# POWER_STAGE.net
KiCad netlist of a schematic drawn in Altium Designer
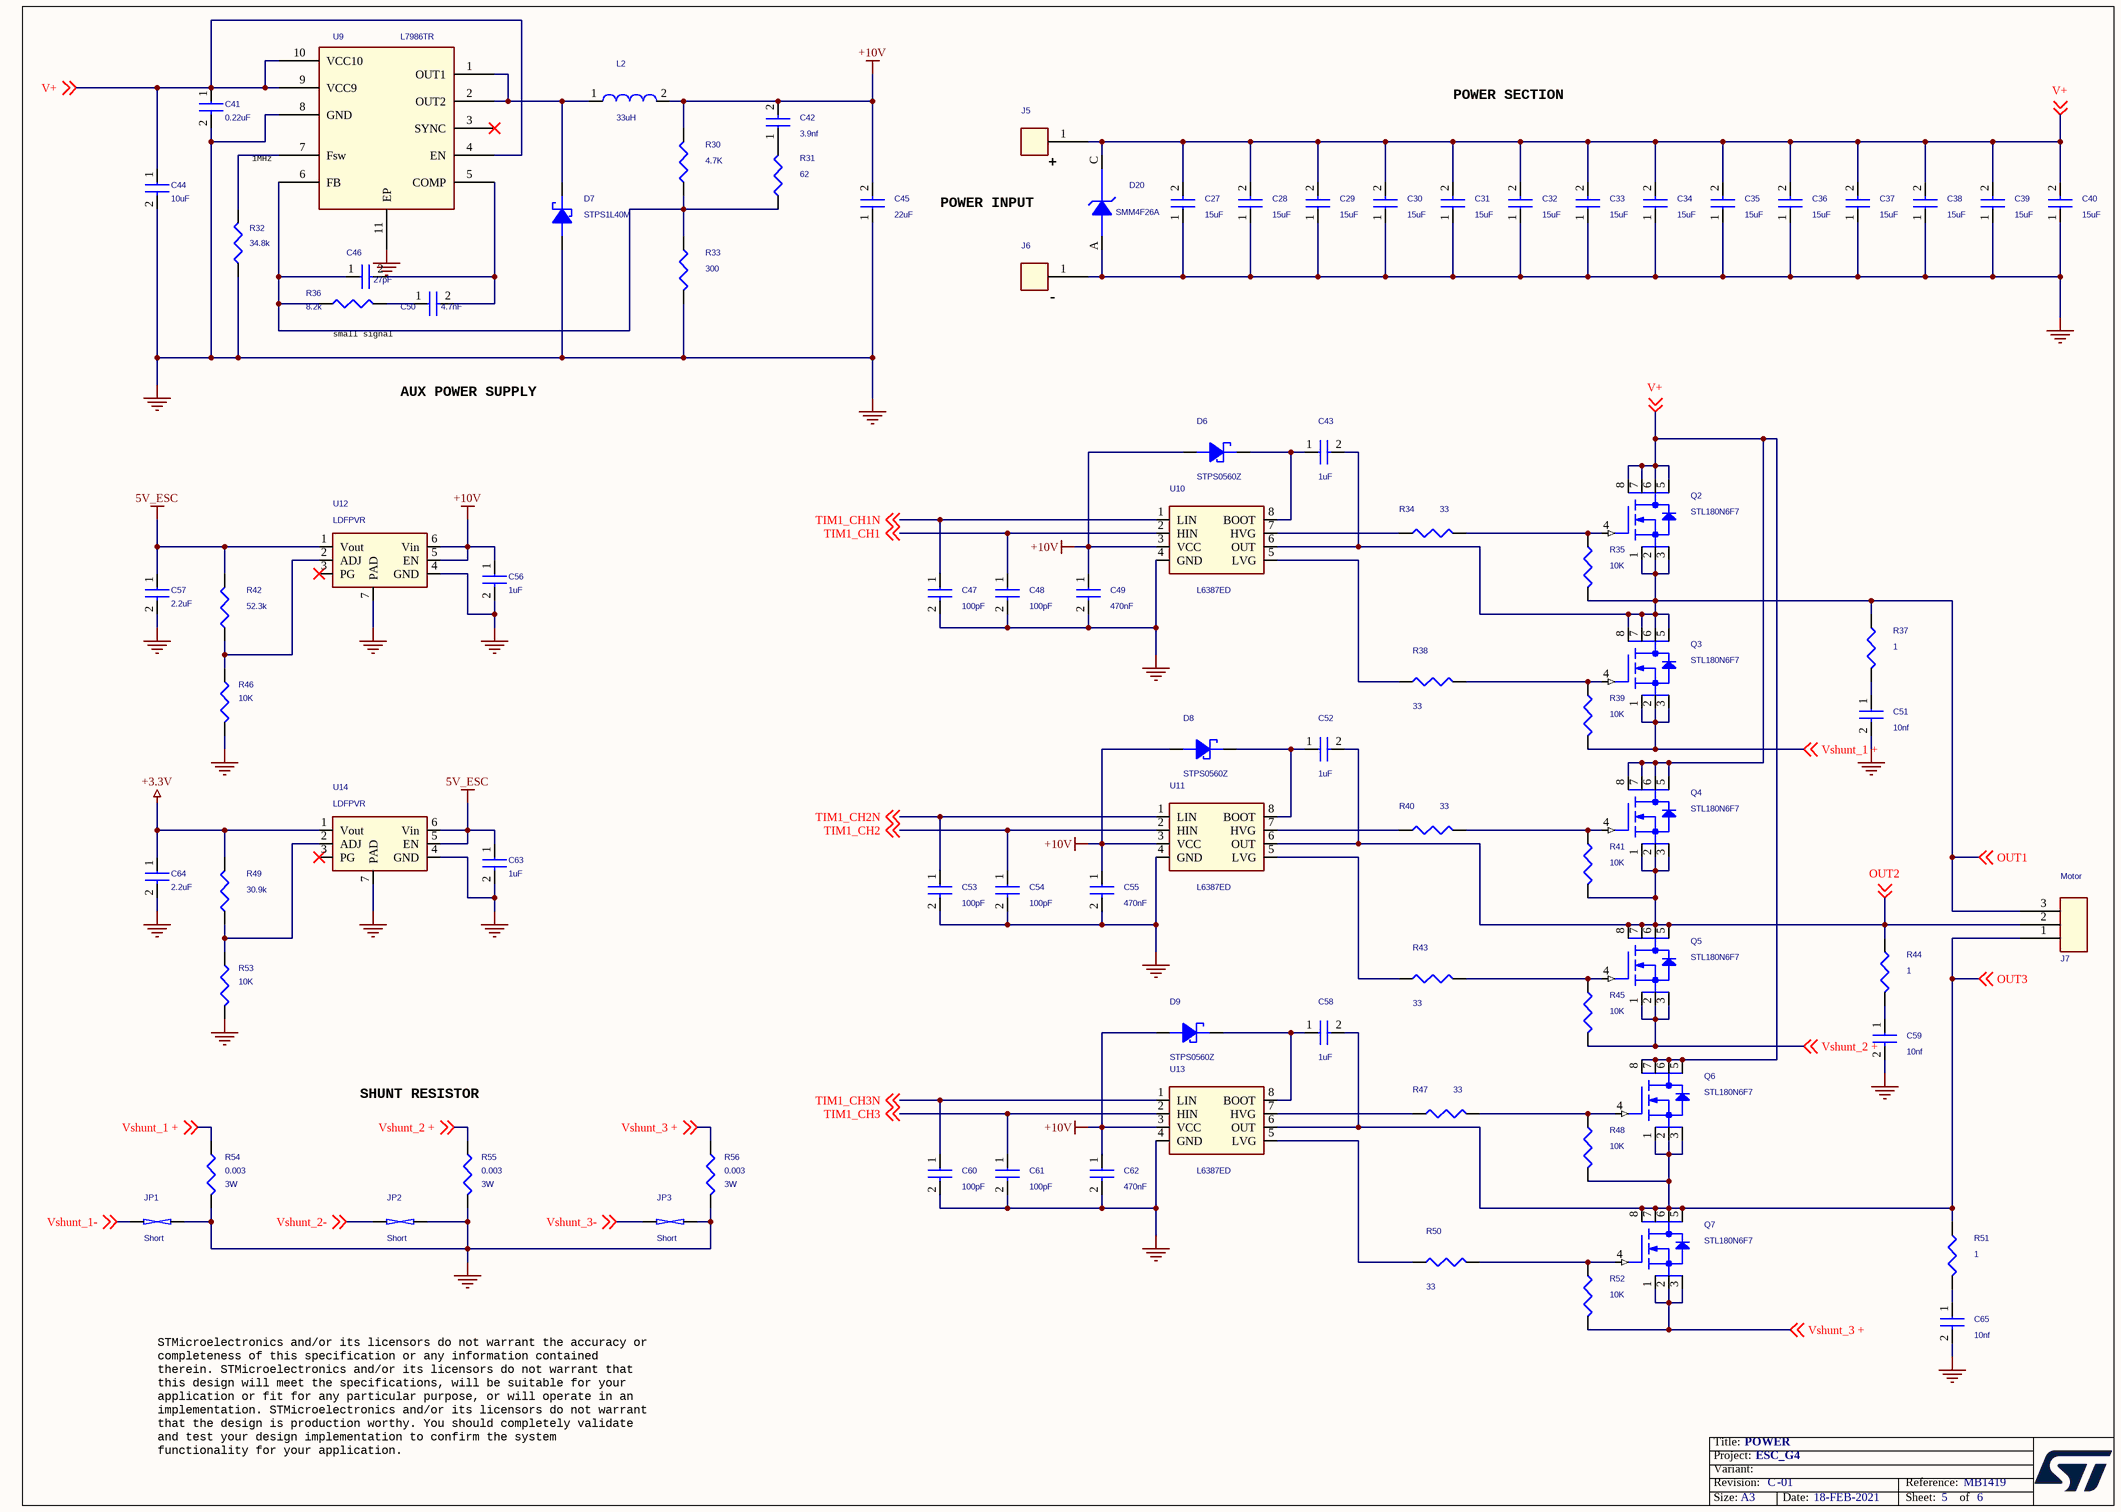
[diagram p0: POWER STAGE.SchDoc]

(export (version "E")
  (design (tool "Eeschema 10.0.6"))
  (components
    (comp (ref "C27")
      (value "15uF")
      (footprint "C_0805_HD")
      (description "CAP CER 15UF 35V X5R 0805")
      (fields (field (name "PART_NUMBER") "TMP-773") (field (name "TOLERANCE") "20%"))
      (libsource (lib "*") (part "CAP_Dup1"))
    )
    (comp (ref "C28")
      (value "15uF")
      (footprint "C_0805_HD")
      (description "CAP CER 15UF 35V X5R 0805")
      (fields (field (name "PART_NUMBER") "TMP-773") (field (name "TOLERANCE") "20%"))
      (libsource (lib "*") (part "CAP_Dup1"))
    )
    (comp (ref "C29")
      (value "15uF")
      (footprint "C_0805_HD")
      (description "CAP CER 15UF 35V X5R 0805")
      (fields (field (name "PART_NUMBER") "TMP-773") (field (name "TOLERANCE") "20%"))
      (libsource (lib "*") (part "CAP_Dup1"))
    )
    (comp (ref "C30")
      (value "15uF")
      (footprint "C_0805_HD")
      (description "CAP CER 15UF 35V X5R 0805")
      (fields (field (name "PART_NUMBER") "TMP-773") (field (name "TOLERANCE") "20%"))
      (libsource (lib "*") (part "CAP_Dup1"))
    )
    (comp (ref "C31")
      (value "15uF")
      (footprint "C_0805_HD")
      (description "CAP CER 15UF 35V X5R 0805")
      (fields (field (name "PART_NUMBER") "TMP-773") (field (name "TOLERANCE") "20%"))
      (libsource (lib "*") (part "CAP_Dup1"))
    )
    (comp (ref "C32")
      (value "15uF")
      (footprint "C_0805_HD")
      (description "CAP CER 15UF 35V X5R 0805")
      (fields (field (name "PART_NUMBER") "TMP-773") (field (name "TOLERANCE") "20%"))
      (libsource (lib "*") (part "CAP_Dup1"))
    )
    (comp (ref "C33")
      (value "15uF")
      (footprint "C_0805_HD")
      (description "CAP CER 15UF 35V X5R 0805")
      (fields (field (name "PART_NUMBER") "TMP-773") (field (name "TOLERANCE") "20%"))
      (libsource (lib "*") (part "CAP_Dup1"))
    )
    (comp (ref "C34")
      (value "15uF")
      (footprint "C_0805_HD")
      (description "CAP CER 15UF 35V X5R 0805")
      (fields (field (name "PART_NUMBER") "TMP-773") (field (name "TOLERANCE") "20%"))
      (libsource (lib "*") (part "CAP_Dup1"))
    )
    (comp (ref "C35")
      (value "15uF")
      (footprint "C_0805_HD")
      (description "CAP CER 15UF 35V X5R 0805")
      (fields (field (name "PART_NUMBER") "TMP-773") (field (name "TOLERANCE") "20%"))
      (libsource (lib "*") (part "CAP_Dup1"))
    )
    (comp (ref "C36")
      (value "15uF")
      (footprint "C_0805_HD")
      (description "CAP CER 15UF 35V X5R 0805")
      (fields (field (name "PART_NUMBER") "TMP-773") (field (name "TOLERANCE") "20%"))
      (libsource (lib "*") (part "CAP_Dup1"))
    )
    (comp (ref "C37")
      (value "15uF")
      (footprint "C_0805_HD")
      (description "CAP CER 15UF 35V X5R 0805")
      (fields (field (name "PART_NUMBER") "TMP-773") (field (name "TOLERANCE") "20%"))
      (libsource (lib "*") (part "CAP_Dup1"))
    )
    (comp (ref "C38")
      (value "15uF")
      (footprint "C_0805_HD")
      (description "CAP CER 15UF 35V X5R 0805")
      (fields (field (name "PART_NUMBER") "TMP-773") (field (name "TOLERANCE") "20%"))
      (libsource (lib "*") (part "CAP_Dup1"))
    )
    (comp (ref "C39")
      (value "15uF")
      (footprint "C_0805_HD")
      (description "CAP CER 15UF 35V X5R 0805")
      (fields (field (name "PART_NUMBER") "TMP-773") (field (name "TOLERANCE") "20%"))
      (libsource (lib "*") (part "CAP_Dup1"))
    )
    (comp (ref "C40")
      (value "15uF")
      (footprint "C_0805_HD")
      (description "CAP CER 15UF 35V X5R 0805")
      (fields (field (name "PART_NUMBER") "TMP-773") (field (name "TOLERANCE") "20%"))
      (libsource (lib "*") (part "CAP_Dup1"))
    )
    (comp (ref "C41")
      (value "0.22uF")
      (footprint "C_0603_HD")
      (description "CAP CER 0.22UF 50V X7R 0603")
      (fields (field (name "MANUFACTURER") "TDK Corporation") (field (name "TOLERANCE") "10%"))
      (libsource (lib "*") (part "CAP_Dup1"))
    )
    (comp (ref "C42")
      (value "3.9nf")
      (footprint "C_0402")
      (description "CAP CER 3900PF 16V X7R 0402")
      (fields (field (name "MANUFACTURER") "KEMET") (field (name "TOLERANCE") "10%"))
      (libsource (lib "*") (part "CAP_Dup1"))
    )
    (comp (ref "C43")
      (value "1uF")
      (footprint "C_0603_HD")
      (description "CAP CER 1UF 25V X7R 0603")
      (fields (field (name "PART_NUMBER") "TMP-446") (field (name "TOLERANCE") "10%"))
      (libsource (lib "*") (part "CAP_Dup1"))
    )
    (comp (ref "C44")
      (value "10uF")
      (footprint "C_1206")
      (description "CAP CER 10UF 50V X7R 1206")
      (fields
        (field (name "MANUFACTURER") "Samsung Electro-Mechanics America, Inc.")
        (field (name "TOLERANCE") "10%")
      )
      (libsource (lib "*") (part "CAP_Dup1"))
    )
    (comp (ref "C45")
      (value "22uF")
      (footprint "C_1206")
      (description "CAP CER 22UF 25V X5R 1206")
      (fields (field (name "MANUFACTURER") "Samsung Electro-Mechanics") (field (name "TOLERANCE") "20%"))
      (libsource (lib "*") (part "CAP_Dup1"))
    )
    (comp (ref "C46")
      (value "27pF")
      (footprint "C_0402")
      (description "CAP CER 27PF 25V C0G/NP0 0402")
      (fields (field (name "MANUFACTURER") "YAGEO") (field (name "TOLERANCE") "5%"))
      (libsource (lib "*") (part "CAP_Dup1"))
    )
    (comp (ref "C47")
      (value "100pF")
      (footprint "C_0402")
      (description "CAP CER 100PF 25V X7R 0402")
      (fields (field (name "PART_NUMBER") "TMP-426") (field (name "TOLERANCE") "10%"))
      (libsource (lib "*") (part "CAP_Dup1"))
    )
    (comp (ref "C48")
      (value "100pF")
      (footprint "C_0402")
      (description "CAP CER 100PF 25V X7R 0402")
      (fields (field (name "PART_NUMBER") "TMP-426") (field (name "TOLERANCE") "10%"))
      (libsource (lib "*") (part "CAP_Dup1"))
    )
    (comp (ref "C49")
      (value "470nF")
      (footprint "C_0603_HD")
      (description "CAP CER 0.47UF 25V X7R 0603")
      (fields (field (name "PART_NUMBER") "TMP-428") (field (name "TOLERANCE") "10%"))
      (libsource (lib "*") (part "CAP_Dup1"))
    )
    (comp (ref "C50")
      (value "4.7nF")
      (footprint "C_0402")
      (description "CAP CER 4700PF 16V X7R 0402")
      (fields (field (name "MANUFACTURER") "Wurth Electronics Inc.") (field (name "TOLERANCE") "10%"))
      (libsource (lib "*") (part "CAP_Dup1"))
    )
    (comp (ref "C51")
      (value "10nf")
      (footprint "C_0603")
      (description "CAP CER 10000PF 100V X7R 0603")
      (fields (field (name "PART_NUMBER") "CAP-00000040") (field (name "TOLERANCE") "20%"))
      (libsource (lib "*") (part "CAP_Dup1"))
    )
    (comp (ref "C52")
      (value "1uF")
      (footprint "C_0603_HD")
      (description "CAP CER 1UF 25V X7R 0603")
      (fields (field (name "PART_NUMBER") "TMP-446") (field (name "TOLERANCE") "10%"))
      (libsource (lib "*") (part "CAP_Dup1"))
    )
    (comp (ref "C53")
      (value "100pF")
      (footprint "C_0402")
      (description "CAP CER 100PF 25V X7R 0402")
      (fields (field (name "PART_NUMBER") "TMP-426") (field (name "TOLERANCE") "10%"))
      (libsource (lib "*") (part "CAP_Dup1"))
    )
    (comp (ref "C54")
      (value "100pF")
      (footprint "C_0402")
      (description "CAP CER 100PF 25V X7R 0402")
      (fields (field (name "PART_NUMBER") "TMP-426") (field (name "TOLERANCE") "10%"))
      (libsource (lib "*") (part "CAP_Dup1"))
    )
    (comp (ref "C55")
      (value "470nF")
      (footprint "C_0603_HD")
      (description "CAP CER 0.47UF 25V X7R 0603")
      (fields (field (name "PART_NUMBER") "TMP-428") (field (name "TOLERANCE") "10%"))
      (libsource (lib "*") (part "CAP_Dup1"))
    )
    (comp (ref "C56")
      (value "1uF")
      (footprint "C_0402")
      (description "CAP CER 1UF 25V X5R 0402")
      (fields
        (field (name "MANUFACTURER") "Murata Electronics North America")
        (field (name "TOLERANCE") "10%")
      )
      (libsource (lib "*") (part "CAP_Dup1"))
    )
    (comp (ref "C57")
      (value "2.2uF")
      (footprint "C_0402")
      (description "CAP CER 2.2UF 10V X5R 0402")
      (fields (field (name "PART_NUMBER") "TMP-449") (field (name "TOLERANCE") "20%"))
      (libsource (lib "*") (part "CAP_Dup1"))
    )
    (comp (ref "C58")
      (value "1uF")
      (footprint "C_0603_HD")
      (description "CAP CER 1UF 25V X7R 0603")
      (fields (field (name "PART_NUMBER") "TMP-446") (field (name "TOLERANCE") "10%"))
      (libsource (lib "*") (part "CAP_Dup1"))
    )
    (comp (ref "C59")
      (value "10nf")
      (footprint "C_0603")
      (description "CAP CER 10000PF 100V X7R 0603")
      (fields (field (name "PART_NUMBER") "CAP-00000040") (field (name "TOLERANCE") "20%"))
      (libsource (lib "*") (part "CAP_Dup1"))
    )
    (comp (ref "C60")
      (value "100pF")
      (footprint "C_0402")
      (description "CAP CER 100PF 25V X7R 0402")
      (fields (field (name "PART_NUMBER") "TMP-426") (field (name "TOLERANCE") "10%"))
      (libsource (lib "*") (part "CAP_Dup1"))
    )
    (comp (ref "C61")
      (value "100pF")
      (footprint "C_0402")
      (description "CAP CER 100PF 25V X7R 0402")
      (fields (field (name "PART_NUMBER") "TMP-426") (field (name "TOLERANCE") "10%"))
      (libsource (lib "*") (part "CAP_Dup1"))
    )
    (comp (ref "C62")
      (value "470nF")
      (footprint "C_0603_HD")
      (description "CAP CER 0.47UF 25V X7R 0603")
      (fields (field (name "PART_NUMBER") "TMP-428") (field (name "TOLERANCE") "10%"))
      (libsource (lib "*") (part "CAP_Dup1"))
    )
    (comp (ref "C63")
      (value "1uF")
      (footprint "C_0402")
      (description "CAP CER 1UF 25V X5R 0402")
      (fields
        (field (name "MANUFACTURER") "Murata Electronics North America")
        (field (name "TOLERANCE") "10%")
      )
      (libsource (lib "*") (part "CAP_Dup1"))
    )
    (comp (ref "C64")
      (value "2.2uF")
      (footprint "C_0402")
      (description "CAP CER 2.2UF 10V X5R 0402")
      (fields (field (name "PART_NUMBER") "TMP-449") (field (name "TOLERANCE") "20%"))
      (libsource (lib "*") (part "CAP_Dup1"))
    )
    (comp (ref "C65")
      (value "10nf")
      (footprint "C_0603")
      (description "CAP CER 10000PF 100V X7R 0603")
      (fields (field (name "PART_NUMBER") "CAP-00000040") (field (name "TOLERANCE") "20%"))
      (libsource (lib "*") (part "CAP_Dup1"))
    )
    (comp (ref "D6")
      (value "STPS0560Z")
      (footprint "SOD_123")
      (description "DIODE SCHOTTKY 60V 500MA SOD123")
      (fields (field (name "MANUFACTURER") "STMicroelectronics") (field (name "PART_NUMBER") "TMP-373"))
      (libsource (lib "*") (part "DIODE_SCHOTTKY_0"))
    )
    (comp (ref "D7")
      (value "STPS1L40M")
      (footprint "do216-aa_stmite")
      (description "DIODE SCHOTTKY 40V 1A STMITE")
      (fields (field (name "PART_NUMBER") "TMP-372") (field (name "MANUFACTURER") "STMicroelectronics"))
      (libsource (lib "*") (part "DIODE_SCHOTTKY_0"))
    )
    (comp (ref "D8")
      (value "STPS0560Z")
      (footprint "SOD_123")
      (description "DIODE SCHOTTKY 60V 500MA SOD123")
      (fields (field (name "MANUFACTURER") "STMicroelectronics") (field (name "PART_NUMBER") "TMP-373"))
      (libsource (lib "*") (part "DIODE_SCHOTTKY_0"))
    )
    (comp (ref "D9")
      (value "STPS0560Z")
      (footprint "SOD_123")
      (description "DIODE SCHOTTKY 60V 500MA SOD123")
      (fields (field (name "MANUFACTURER") "STMicroelectronics") (field (name "PART_NUMBER") "TMP-373"))
      (libsource (lib "*") (part "DIODE_SCHOTTKY_0"))
    )
    (comp (ref "D20")
      (value "SMM4F26A")
      (footprint "do216-aa-flat")
      (description "TVS DIODE 26VWM 53.5VC DO222AA")
      (fields (field (name "MANUFACTURER") "STMicroelectronics") (field (name "PART_NUMBER") "TMP-376"))
      (libsource (lib "*") (part "DIODE_TRANSIL_UNI_0"))
    )
    (comp (ref "J5")
      (value "CON1")
      (footprint "wire1_220s")
      (description "SOLDER PADS")
      (libsource (lib "*") (part "CON1"))
    )
    (comp (ref "J6")
      (value "CON1")
      (footprint "wire1_220s")
      (description "SOLDER PADS")
      (libsource (lib "*") (part "CON1"))
    )
    (comp (ref "J7")
      (value "Motor")
      (footprint "conn_motor_out")
      (description "SOLDER PADS")
      (libsource (lib "*") (part "CON3"))
    )
    (comp (ref "JP1")
      (value "Short")
      (footprint "SHORT")
      (description "2 PIN SHORTED TO CONNECT DIFFERENT NETS")
      (fields (field (name "PART_NUMBER") "TMP-442"))
      (libsource (lib "*") (part "SHORT"))
    )
    (comp (ref "JP2")
      (value "Short")
      (footprint "SHORT")
      (description "2 PIN SHORTED TO CONNECT DIFFERENT NETS")
      (fields (field (name "PART_NUMBER") "TMP-442"))
      (libsource (lib "*") (part "SHORT"))
    )
    (comp (ref "JP3")
      (value "Short")
      (footprint "SHORT")
      (description "2 PIN SHORTED TO CONNECT DIFFERENT NETS")
      (fields (field (name "PART_NUMBER") "TMP-442"))
      (libsource (lib "*") (part "SHORT"))
    )
    (comp (ref "L2")
      (value "33uH")
      (footprint "ind_Coilcraft-LPS4018")
      (description "Fixed Inductors LPS4018 Low Profile 33uH 0.8A 20% SMD")
      (fields (field (name "MANUFACTURER") "Coilcraft") (field (name "TOLERANCE") "20%"))
      (libsource (lib "*") (part "IND"))
    )
    (comp (ref "Q2")
      (value "STL180N6F7")
      (footprint "power_flat_5x6")
      (description "N-channel 60 V, 1.9 mO typ., 120 A STripFET™ F7")
      (fields (field (name "PART_NUMBER") "TMP-772") (field (name "MANUFACTURER") "STMicroelectronics"))
      (libsource (lib "*") (part "MOSFET_N_DIODE_SSSGDDDD"))
    )
    (comp (ref "Q3")
      (value "STL180N6F7")
      (footprint "power_flat_5x6")
      (description "N-channel 60 V, 1.9 mO typ., 120 A STripFET™ F7")
      (fields (field (name "PART_NUMBER") "TMP-772") (field (name "MANUFACTURER") "STMicroelectronics"))
      (libsource (lib "*") (part "MOSFET_N_DIODE_SSSGDDDD"))
    )
    (comp (ref "Q4")
      (value "STL180N6F7")
      (footprint "power_flat_5x6")
      (description "N-channel 60 V, 1.9 mO typ., 120 A STripFET™ F7")
      (fields (field (name "PART_NUMBER") "TMP-772") (field (name "MANUFACTURER") "STMicroelectronics"))
      (libsource (lib "*") (part "MOSFET_N_DIODE_SSSGDDDD"))
    )
    (comp (ref "Q5")
      (value "STL180N6F7")
      (footprint "power_flat_5x6")
      (description "N-channel 60 V, 1.9 mO typ., 120 A STripFET™ F7")
      (fields (field (name "PART_NUMBER") "TMP-772") (field (name "MANUFACTURER") "STMicroelectronics"))
      (libsource (lib "*") (part "MOSFET_N_DIODE_SSSGDDDD"))
    )
    (comp (ref "Q6")
      (value "STL180N6F7")
      (footprint "power_flat_5x6")
      (description "N-channel 60 V, 1.9 mO typ., 120 A STripFET™ F7")
      (fields (field (name "PART_NUMBER") "TMP-772") (field (name "MANUFACTURER") "STMicroelectronics"))
      (libsource (lib "*") (part "MOSFET_N_DIODE_SSSGDDDD"))
    )
    (comp (ref "Q7")
      (value "STL180N6F7")
      (footprint "power_flat_5x6")
      (description "N-channel 60 V, 1.9 mO typ., 120 A STripFET™ F7")
      (fields (field (name "PART_NUMBER") "TMP-772") (field (name "MANUFACTURER") "STMicroelectronics"))
      (libsource (lib "*") (part "MOSFET_N_DIODE_SSSGDDDD"))
    )
    (comp (ref "R30")
      (value "4.7K")
      (footprint "R_0402")
      (description "RES SMD 4.7K OHM 1% 1/16W 0402")
      (fields (field (name "MANUFACTURER") "TE Connectivity Passive Product") (field (name "TOLERANCE") "1%"))
      (libsource (lib "*") (part "RES"))
    )
    (comp (ref "R31")
      (value "62")
      (footprint "R_0402")
      (description "RES SMD 62 OHM 1% 1/16W 0402")
      (fields (field (name "MANUFACTURER") "Yageo") (field (name "TOLERANCE") "1%"))
      (libsource (lib "*") (part "RES"))
    )
    (comp (ref "R32")
      (value "34.8k")
      (footprint "R_0402")
      (description "RES SMD 34.8K OHM 1% 1/16W 0402")
      (fields (field (name "MANUFACTURER") "Yageo") (field (name "TOLERANCE") "1%"))
      (libsource (lib "*") (part "RES"))
    )
    (comp (ref "R33")
      (value "300")
      (footprint "R_0402")
      (description "RES SMD 300 OHM 1% 1/16W 0402")
      (fields (field (name "PART_NUMBER") "TMP-418") (field (name "TOLERANCE") "1%"))
      (libsource (lib "*") (part "RES"))
    )
    (comp (ref "R34")
      (value "33")
      (footprint "R_0603_HD")
      (description "RES SMD 33 OHM 1% 1/10W 0603")
      (fields (field (name "MANUFACTURER") "Yageo") (field (name "TOLERANCE") "1%"))
      (libsource (lib "*") (part "RES"))
    )
    (comp (ref "R35")
      (value "10K")
      (footprint "R_0402")
      (description "RES SMD 10K OHM 1% 1/16W 0402")
      (fields (field (name "MANUFACTURER") "Yageo") (field (name "TOLERANCE") "1%"))
      (libsource (lib "*") (part "RES"))
    )
    (comp (ref "R36")
      (value "8.2k")
      (footprint "R_0402")
      (description "RES SMD 8.2K OHM 5% 1/16W 0402")
      (fields (field (name "MANUFACTURER") "Yageo") (field (name "TOLERANCE") "5%"))
      (libsource (lib "*") (part "RES"))
    )
    (comp (ref "R37")
      (value "1")
      (footprint "R_0805")
      (description "RES SMD 1 OHM 5% 1/8W 0805")
      (fields (field (name "PART_NUMBER") "TMP-430") (field (name "TOLERANCE") "5%"))
      (libsource (lib "*") (part "RES"))
    )
    (comp (ref "R38")
      (value "33")
      (footprint "R_0603_HD")
      (description "RES SMD 33 OHM 1% 1/10W 0603")
      (fields (field (name "PART_NUMBER") "TMP-266") (field (name "TOLERANCE") "1%"))
      (libsource (lib "*") (part "RES"))
    )
    (comp (ref "R39")
      (value "10K")
      (footprint "R_0402")
      (description "RES SMD 10K OHM 1% 1/16W 0402")
      (fields (field (name "MANUFACTURER") "Yageo") (field (name "TOLERANCE") "1%"))
      (libsource (lib "*") (part "RES"))
    )
    (comp (ref "R40")
      (value "33")
      (footprint "R_0603_HD")
      (description "RES SMD 33 OHM 1% 1/10W 0603")
      (fields (field (name "MANUFACTURER") "Yageo") (field (name "TOLERANCE") "1%"))
      (libsource (lib "*") (part "RES"))
    )
    (comp (ref "R41")
      (value "10K")
      (footprint "R_0402")
      (description "RES SMD 10K OHM 1% 1/16W 0402")
      (fields (field (name "MANUFACTURER") "Yageo") (field (name "TOLERANCE") "1%"))
      (libsource (lib "*") (part "RES"))
    )
    (comp (ref "R42")
      (value "52.3k")
      (footprint "R_0402")
      (description "RES SMD 52.3K OHM 1% 1/16W 0402")
      (fields (field (name "MANUFACTURER") "Samsung Electro-Mechanics") (field (name "TOLERANCE") "1%"))
      (libsource (lib "*") (part "RES"))
    )
    (comp (ref "R43")
      (value "33")
      (footprint "R_0603_HD")
      (description "RES SMD 33 OHM 1% 1/10W 0603")
      (fields (field (name "PART_NUMBER") "TMP-266") (field (name "TOLERANCE") "1%"))
      (libsource (lib "*") (part "RES"))
    )
    (comp (ref "R44")
      (value "1")
      (footprint "R_0805")
      (description "RES SMD 1 OHM 5% 1/8W 0805")
      (fields (field (name "PART_NUMBER") "TMP-430") (field (name "TOLERANCE") "5%"))
      (libsource (lib "*") (part "RES"))
    )
    (comp (ref "R45")
      (value "10K")
      (footprint "R_0402")
      (description "RES SMD 10K OHM 1% 1/16W 0402")
      (fields (field (name "MANUFACTURER") "Yageo") (field (name "TOLERANCE") "1%"))
      (libsource (lib "*") (part "RES"))
    )
    (comp (ref "R46")
      (value "10K")
      (footprint "R_0402")
      (description "RES SMD 10K OHM 1% 1/16W 0402")
      (fields (field (name "PART_NUMBER") "TMP-396") (field (name "TOLERANCE") "1%"))
      (libsource (lib "*") (part "RES"))
    )
    (comp (ref "R47")
      (value "33")
      (footprint "R_0603_HD")
      (description "RES SMD 33 OHM 1% 1/10W 0603")
      (fields (field (name "PART_NUMBER") "TMP-266") (field (name "TOLERANCE") "1%"))
      (libsource (lib "*") (part "RES"))
    )
    (comp (ref "R48")
      (value "10K")
      (footprint "R_0402")
      (description "RES SMD 10K OHM 1% 1/16W 0402")
      (fields (field (name "PART_NUMBER") "TMP-396") (field (name "TOLERANCE") "1%"))
      (libsource (lib "*") (part "RES"))
    )
    (comp (ref "R49")
      (value "30.9k")
      (footprint "R_0402")
      (description "RES SMD 30.9K OHM 1% 1/10W 0402")
      (fields (field (name "PART_NUMBER") "TMP-448") (field (name "TOLERANCE") "1%"))
      (libsource (lib "*") (part "RES"))
    )
    (comp (ref "R50")
      (value "33")
      (footprint "R_0603_HD")
      (description "RES SMD 33 OHM 1% 1/10W 0603")
      (fields (field (name "PART_NUMBER") "TMP-266") (field (name "TOLERANCE") "1%"))
      (libsource (lib "*") (part "RES"))
    )
    (comp (ref "R51")
      (value "1")
      (footprint "R_0805")
      (description "RES SMD 1 OHM 5% 1/8W 0805")
      (fields (field (name "PART_NUMBER") "TMP-430") (field (name "TOLERANCE") "5%"))
      (libsource (lib "*") (part "RES"))
    )
    (comp (ref "R52")
      (value "10K")
      (footprint "R_0402")
      (description "RES SMD 10K OHM 1% 1/16W 0402")
      (fields (field (name "PART_NUMBER") "TMP-396") (field (name "TOLERANCE") "1%"))
      (libsource (lib "*") (part "RES"))
    )
    (comp (ref "R53")
      (value "10K")
      (footprint "R_0402")
      (description "RES SMD 10K OHM 1% 1/16W 0402")
      (fields (field (name "PART_NUMBER") "TMP-396") (field (name "TOLERANCE") "1%"))
      (libsource (lib "*") (part "RES"))
    )
    (comp (ref "R54")
      (value "0.003")
      (footprint "resc635x300x60l193n")
      (description "RES 0.003 OHM 1% 3W 2512")
      (fields
        (field (name "PART_NUMBER") "TMP-766")
        (field (name "TOLERANCE") "1%")
        (field (name "RATED POWER") "3W")
      )
      (libsource (lib "*") (part "RES"))
    )
    (comp (ref "R55")
      (value "0.003")
      (footprint "resc635x300x60l193n")
      (description "RES 0.003 OHM 1% 3W 2512")
      (fields
        (field (name "MANUFACTURER") "ROHM")
        (field (name "RATED POWER") "3W")
        (field (name "TOLERANCE") "1%")
      )
      (libsource (lib "*") (part "RES"))
    )
    (comp (ref "R56")
      (value "0.003")
      (footprint "resc635x300x60l193n")
      (description "RES 0.003 OHM 1% 3W 2512")
      (fields
        (field (name "PART_NUMBER") "TMP-766")
        (field (name "TOLERANCE") "1%")
        (field (name "RATED POWER") "3W")
      )
      (libsource (lib "*") (part "RES"))
    )
    (comp (ref "U9")
      (value "L7986TR")
      (footprint "son11p50_300x300x100l40x24t2-1")
      (description "IC REG BUCK ADJ 3A 10VDFPN")
      (fields (field (name "MANUFACTURER") "STMicroelectronics") (field (name "PART_NUMBER") "TMP-362"))
      (libsource (lib "*") (part "L7986TR"))
    )
    (comp (ref "U10")
      (value "L6387ED")
      (footprint "SOIC8P127_490X600X175L83X42N")
      (description "IC DRIVER HI/LO SIDE HV 8-SOIC")
      (fields (field (name "MANUFACTURER") "STMicroelectronics") (field (name "PART_NUMBER") "TMP-367"))
      (libsource (lib "*") (part "L6387E"))
    )
    (comp (ref "U11")
      (value "L6387ED")
      (footprint "SOIC8P127_490X600X175L83X42N")
      (description "IC DRIVER HI/LO SIDE HV 8-SOIC")
      (fields (field (name "PART_NUMBER") "TMP-367") (field (name "MANUFACTURER") "STMicroelectronics"))
      (libsource (lib "*") (part "L6387E"))
    )
    (comp (ref "U12")
      (value "LDFPVR")
      (footprint "son7p65_200x200x100l25x30t18-1")
      (description "IC REG LINEAR POS ADJ 1A 6DFN")
      (fields (field (name "PART_NUMBER") "TMP-450") (field (name "MANUFACTURER") "STMicroelectronics"))
      (libsource (lib "*") (part "LDFPxR"))
    )
    (comp (ref "U13")
      (value "L6387ED")
      (footprint "SOIC8P127_490X600X175L83X42N")
      (description "IC DRIVER HI/LO SIDE HV 8-SOIC")
      (fields (field (name "PART_NUMBER") "TMP-367") (field (name "MANUFACTURER") "STMicroelectronics"))
      (libsource (lib "*") (part "L6387E"))
    )
    (comp (ref "U14")
      (value "LDFPVR")
      (footprint "son7p65_200x200x100l25x30t18-1")
      (description "IC REG LINEAR POS ADJ 1A 6DFN")
      (fields (field (name "MANUFACTURER") "STMicroelectronics") (field (name "PART_NUMBER") "TMP-450"))
      (libsource (lib "*") (part "LDFPxR"))
    )
  )
  (nets
    (net (code "1") (name "+3.3V") (class "Default")
      (node (ref "C64") (pin "1") (pinfunction "1_1") (pintype "passive"))
      (node (ref "R49") (pin "2") (pinfunction "2_2") (pintype "passive"))
      (node (ref "U14") (pin "1") (pinfunction "Vout_1") (pintype "passive"))
    )
    (net (code "2") (name "+10V") (class "Default")
      (node (ref "C42") (pin "2") (pinfunction "2_2") (pintype "passive"))
      (node (ref "C45") (pin "2") (pinfunction "2_2") (pintype "passive"))
      (node (ref "C49") (pin "1") (pinfunction "1_1") (pintype "passive"))
      (node (ref "C55") (pin "1") (pinfunction "1_1") (pintype "passive"))
      (node (ref "C56") (pin "1") (pinfunction "1_1") (pintype "passive"))
      (node (ref "C62") (pin "1") (pinfunction "1_1") (pintype "passive"))
      (node (ref "D6") (pin "A") (pinfunction "A_A") (pintype "passive"))
      (node (ref "D8") (pin "A") (pinfunction "A_A") (pintype "passive"))
      (node (ref "D9") (pin "A") (pinfunction "A_A") (pintype "passive"))
      (node (ref "L2") (pin "2") (pinfunction "2_2") (pintype "passive"))
      (node (ref "R30") (pin "1") (pinfunction "1_1") (pintype "passive"))
      (node (ref "U10") (pin "3") (pinfunction "VCC_3") (pintype "passive"))
      (node (ref "U11") (pin "3") (pinfunction "VCC_3") (pintype "passive"))
      (node (ref "U12") (pin "5") (pinfunction "EN_5") (pintype "passive"))
      (node (ref "U12") (pin "6") (pinfunction "Vin_6") (pintype "passive"))
      (node (ref "U13") (pin "3") (pinfunction "VCC_3") (pintype "passive"))
    )
    (net (code "3") (name "5V_ESC") (class "Default")
      (node (ref "C57") (pin "1") (pinfunction "1_1") (pintype "passive"))
      (node (ref "C63") (pin "1") (pinfunction "1_1") (pintype "passive"))
      (node (ref "R42") (pin "2") (pinfunction "2_2") (pintype "passive"))
      (node (ref "U12") (pin "1") (pinfunction "Vout_1") (pintype "passive"))
      (node (ref "U14") (pin "5") (pinfunction "EN_5") (pintype "passive"))
      (node (ref "U14") (pin "6") (pinfunction "Vin_6") (pintype "passive"))
    )
    (net (code "4") (name "GND") (class "Default")
      (node (ref "C27") (pin "1") (pinfunction "1_1") (pintype "passive"))
      (node (ref "C28") (pin "1") (pinfunction "1_1") (pintype "passive"))
      (node (ref "C29") (pin "1") (pinfunction "1_1") (pintype "passive"))
      (node (ref "C30") (pin "1") (pinfunction "1_1") (pintype "passive"))
      (node (ref "C31") (pin "1") (pinfunction "1_1") (pintype "passive"))
      (node (ref "C32") (pin "1") (pinfunction "1_1") (pintype "passive"))
      (node (ref "C33") (pin "1") (pinfunction "1_1") (pintype "passive"))
      (node (ref "C34") (pin "1") (pinfunction "1_1") (pintype "passive"))
      (node (ref "C35") (pin "1") (pinfunction "1_1") (pintype "passive"))
      (node (ref "C36") (pin "1") (pinfunction "1_1") (pintype "passive"))
      (node (ref "C37") (pin "1") (pinfunction "1_1") (pintype "passive"))
      (node (ref "C38") (pin "1") (pinfunction "1_1") (pintype "passive"))
      (node (ref "C39") (pin "1") (pinfunction "1_1") (pintype "passive"))
      (node (ref "C40") (pin "1") (pinfunction "1_1") (pintype "passive"))
      (node (ref "C41") (pin "2") (pinfunction "2_2") (pintype "passive"))
      (node (ref "C44") (pin "2") (pinfunction "2_2") (pintype "passive"))
      (node (ref "C45") (pin "1") (pinfunction "1_1") (pintype "passive"))
      (node (ref "C47") (pin "2") (pinfunction "2_2") (pintype "passive"))
      (node (ref "C48") (pin "2") (pinfunction "2_2") (pintype "passive"))
      (node (ref "C49") (pin "2") (pinfunction "2_2") (pintype "passive"))
      (node (ref "C51") (pin "2") (pinfunction "2_2") (pintype "passive"))
      (node (ref "C53") (pin "2") (pinfunction "2_2") (pintype "passive"))
      (node (ref "C54") (pin "2") (pinfunction "2_2") (pintype "passive"))
      (node (ref "C55") (pin "2") (pinfunction "2_2") (pintype "passive"))
      (node (ref "C56") (pin "2") (pinfunction "2_2") (pintype "passive"))
      (node (ref "C57") (pin "2") (pinfunction "2_2") (pintype "passive"))
      (node (ref "C59") (pin "2") (pinfunction "2_2") (pintype "passive"))
      (node (ref "C60") (pin "2") (pinfunction "2_2") (pintype "passive"))
      (node (ref "C61") (pin "2") (pinfunction "2_2") (pintype "passive"))
      (node (ref "C62") (pin "2") (pinfunction "2_2") (pintype "passive"))
      (node (ref "C63") (pin "2") (pinfunction "2_2") (pintype "passive"))
      (node (ref "C64") (pin "2") (pinfunction "2_2") (pintype "passive"))
      (node (ref "C65") (pin "2") (pinfunction "2_2") (pintype "passive"))
      (node (ref "D20") (pin "A") (pinfunction "A_A") (pintype "passive"))
      (node (ref "D7") (pin "A") (pinfunction "A_A") (pintype "passive"))
      (node (ref "J6") (pin "1") (pinfunction "1_1") (pintype "passive"))
      (node (ref "JP1") (pin "2") (pinfunction "2_2") (pintype "passive"))
      (node (ref "JP2") (pin "2") (pinfunction "2_2") (pintype "passive"))
      (node (ref "JP3") (pin "2") (pinfunction "2_2") (pintype "passive"))
      (node (ref "R32") (pin "2") (pinfunction "2_2") (pintype "passive"))
      (node (ref "R33") (pin "1") (pinfunction "1_1") (pintype "passive"))
      (node (ref "R46") (pin "2") (pinfunction "2_2") (pintype "passive"))
      (node (ref "R53") (pin "2") (pinfunction "2_2") (pintype "passive"))
      (node (ref "R54") (pin "2") (pinfunction "2_2") (pintype "passive"))
      (node (ref "R55") (pin "2") (pinfunction "2_2") (pintype "passive"))
      (node (ref "R56") (pin "2") (pinfunction "2_2") (pintype "passive"))
      (node (ref "U10") (pin "4") (pinfunction "GND_4") (pintype "passive"))
      (node (ref "U11") (pin "4") (pinfunction "GND_4") (pintype "passive"))
      (node (ref "U12") (pin "4") (pinfunction "GND_4") (pintype "passive"))
      (node (ref "U12") (pin "7") (pinfunction "PAD_7") (pintype "passive"))
      (node (ref "U13") (pin "4") (pinfunction "GND_4") (pintype "passive"))
      (node (ref "U14") (pin "4") (pinfunction "GND_4") (pintype "passive"))
      (node (ref "U14") (pin "7") (pinfunction "PAD_7") (pintype "passive"))
      (node (ref "U9") (pin "11") (pinfunction "EP_11") (pintype "passive"))
      (node (ref "U9") (pin "8") (pinfunction "GND_8") (pintype "passive"))
    )
    (net (code "5") (name "Net-(C42-Pad1)") (class "Default")
      (node (ref "C42") (pin "1") (pinfunction "1_1") (pintype "passive"))
      (node (ref "R31") (pin "1") (pinfunction "1_1") (pintype "passive"))
    )
    (net (code "6") (name "Net-(C50-Pad1)") (class "Default")
      (node (ref "C50") (pin "1") (pinfunction "1_1") (pintype "passive"))
      (node (ref "R36") (pin "1") (pinfunction "1_1") (pintype "passive"))
    )
    (net (code "7") (name "Net-(C51-Pad1)") (class "Default")
      (node (ref "C51") (pin "1") (pinfunction "1_1") (pintype "passive"))
      (node (ref "R37") (pin "2") (pinfunction "2_2") (pintype "passive"))
    )
    (net (code "8") (name "Net-(C59-Pad1)") (class "Default")
      (node (ref "C59") (pin "1") (pinfunction "1_1") (pintype "passive"))
      (node (ref "R44") (pin "2") (pinfunction "2_2") (pintype "passive"))
    )
    (net (code "9") (name "Net-(C65-Pad1)") (class "Default")
      (node (ref "C65") (pin "1") (pinfunction "1_1") (pintype "passive"))
      (node (ref "R51") (pin "2") (pinfunction "2_2") (pintype "passive"))
    )
    (net (code "10") (name "Net-(Q2-G)") (class "Default")
      (node (ref "Q2") (pin "4") (pinfunction "G_4") (pintype "input"))
      (node (ref "R34") (pin "2") (pinfunction "2_2") (pintype "passive"))
      (node (ref "R35") (pin "1") (pinfunction "1_1") (pintype "passive"))
    )
    (net (code "11") (name "Net-(Q3-G)") (class "Default")
      (node (ref "Q3") (pin "4") (pinfunction "G_4") (pintype "input"))
      (node (ref "R38") (pin "2") (pinfunction "2_2") (pintype "passive"))
      (node (ref "R39") (pin "1") (pinfunction "1_1") (pintype "passive"))
    )
    (net (code "12") (name "Net-(Q4-G)") (class "Default")
      (node (ref "Q4") (pin "4") (pinfunction "G_4") (pintype "input"))
      (node (ref "R40") (pin "2") (pinfunction "2_2") (pintype "passive"))
      (node (ref "R41") (pin "1") (pinfunction "1_1") (pintype "passive"))
    )
    (net (code "13") (name "Net-(Q5-G)") (class "Default")
      (node (ref "Q5") (pin "4") (pinfunction "G_4") (pintype "input"))
      (node (ref "R43") (pin "2") (pinfunction "2_2") (pintype "passive"))
      (node (ref "R45") (pin "1") (pinfunction "1_1") (pintype "passive"))
    )
    (net (code "14") (name "Net-(Q6-G)") (class "Default")
      (node (ref "Q6") (pin "4") (pinfunction "G_4") (pintype "input"))
      (node (ref "R47") (pin "2") (pinfunction "2_2") (pintype "passive"))
      (node (ref "R48") (pin "1") (pinfunction "1_1") (pintype "passive"))
    )
    (net (code "15") (name "Net-(Q7-G)") (class "Default")
      (node (ref "Q7") (pin "4") (pinfunction "G_4") (pintype "input"))
      (node (ref "R50") (pin "2") (pinfunction "2_2") (pintype "passive"))
      (node (ref "R52") (pin "1") (pinfunction "1_1") (pintype "passive"))
    )
    (net (code "16") (name "Net-(U9-COMP)") (class "Default")
      (node (ref "C46") (pin "2") (pinfunction "2_2") (pintype "passive"))
      (node (ref "C50") (pin "2") (pinfunction "2_2") (pintype "passive"))
      (node (ref "U9") (pin "5") (pinfunction "COMP_5") (pintype "passive"))
    )
    (net (code "17") (name "Net-(U9-FB)") (class "Default")
      (node (ref "C46") (pin "1") (pinfunction "1_1") (pintype "passive"))
      (node (ref "R30") (pin "2") (pinfunction "2_2") (pintype "passive"))
      (node (ref "R31") (pin "2") (pinfunction "2_2") (pintype "passive"))
      (node (ref "R33") (pin "2") (pinfunction "2_2") (pintype "passive"))
      (node (ref "R36") (pin "2") (pinfunction "2_2") (pintype "passive"))
      (node (ref "U9") (pin "6") (pinfunction "FB_6") (pintype "passive"))
    )
    (net (code "18") (name "Net-(U9-Fsw)") (class "Default")
      (node (ref "R32") (pin "1") (pinfunction "1_1") (pintype "passive"))
      (node (ref "U9") (pin "7") (pinfunction "Fsw_7") (pintype "passive"))
    )
    (net (code "19") (name "Net-(U9-OUT1)") (class "Default")
      (node (ref "D7") (pin "C") (pinfunction "C_C") (pintype "passive"))
      (node (ref "L2") (pin "1") (pinfunction "1_1") (pintype "passive"))
      (node (ref "U9") (pin "1") (pinfunction "OUT1_1") (pintype "passive"))
      (node (ref "U9") (pin "2") (pinfunction "OUT2_2") (pintype "passive"))
    )
    (net (code "20") (name "Net-(U10-BOOT)") (class "Default")
      (node (ref "C43") (pin "1") (pinfunction "1_1") (pintype "passive"))
      (node (ref "D6") (pin "C") (pinfunction "C_C") (pintype "passive"))
      (node (ref "U10") (pin "8") (pinfunction "BOOT_8") (pintype "passive"))
    )
    (net (code "21") (name "Net-(U10-HVG)") (class "Default")
      (node (ref "R34") (pin "1") (pinfunction "1_1") (pintype "passive"))
      (node (ref "U10") (pin "7") (pinfunction "HVG_7") (pintype "passive"))
    )
    (net (code "22") (name "Net-(U10-LVG)") (class "Default")
      (node (ref "R38") (pin "1") (pinfunction "1_1") (pintype "passive"))
      (node (ref "U10") (pin "5") (pinfunction "LVG_5") (pintype "passive"))
    )
    (net (code "23") (name "Net-(U11-BOOT)") (class "Default")
      (node (ref "C52") (pin "1") (pinfunction "1_1") (pintype "passive"))
      (node (ref "D8") (pin "C") (pinfunction "C_C") (pintype "passive"))
      (node (ref "U11") (pin "8") (pinfunction "BOOT_8") (pintype "passive"))
    )
    (net (code "24") (name "Net-(U11-HVG)") (class "Default")
      (node (ref "R40") (pin "1") (pinfunction "1_1") (pintype "passive"))
      (node (ref "U11") (pin "7") (pinfunction "HVG_7") (pintype "passive"))
    )
    (net (code "25") (name "Net-(U11-LVG)") (class "Default")
      (node (ref "R43") (pin "1") (pinfunction "1_1") (pintype "passive"))
      (node (ref "U11") (pin "5") (pinfunction "LVG_5") (pintype "passive"))
    )
    (net (code "26") (name "Net-(U12-ADJ)") (class "Default")
      (node (ref "R42") (pin "1") (pinfunction "1_1") (pintype "passive"))
      (node (ref "R46") (pin "1") (pinfunction "1_1") (pintype "passive"))
      (node (ref "U12") (pin "2") (pinfunction "ADJ_2") (pintype "passive"))
    )
    (net (code "27") (name "Net-(U13-BOOT)") (class "Default")
      (node (ref "C58") (pin "1") (pinfunction "1_1") (pintype "passive"))
      (node (ref "D9") (pin "C") (pinfunction "C_C") (pintype "passive"))
      (node (ref "U13") (pin "8") (pinfunction "BOOT_8") (pintype "passive"))
    )
    (net (code "28") (name "Net-(U13-HVG)") (class "Default")
      (node (ref "R47") (pin "1") (pinfunction "1_1") (pintype "passive"))
      (node (ref "U13") (pin "7") (pinfunction "HVG_7") (pintype "passive"))
    )
    (net (code "29") (name "Net-(U13-LVG)") (class "Default")
      (node (ref "R50") (pin "1") (pinfunction "1_1") (pintype "passive"))
      (node (ref "U13") (pin "5") (pinfunction "LVG_5") (pintype "passive"))
    )
    (net (code "30") (name "Net-(U14-ADJ)") (class "Default")
      (node (ref "R49") (pin "1") (pinfunction "1_1") (pintype "passive"))
      (node (ref "R53") (pin "1") (pinfunction "1_1") (pintype "passive"))
      (node (ref "U14") (pin "2") (pinfunction "ADJ_2") (pintype "passive"))
    )
    (net (code "31") (name "OUT1") (class "Default")
      (node (ref "C43") (pin "2") (pinfunction "2_2") (pintype "passive"))
      (node (ref "J7") (pin "3") (pinfunction "3_3") (pintype "passive"))
      (node (ref "Q2") (pin "1") (pinfunction "S1_1") (pintype "passive"))
      (node (ref "Q2") (pin "2") (pinfunction "S2_2") (pintype "passive"))
      (node (ref "Q2") (pin "3") (pinfunction "S3_3") (pintype "passive"))
      (node (ref "Q3") (pin "5") (pinfunction "D_5") (pintype "passive"))
      (node (ref "Q3") (pin "6") (pinfunction "D6_6") (pintype "passive"))
      (node (ref "Q3") (pin "7") (pinfunction "D7_7") (pintype "passive"))
      (node (ref "Q3") (pin "8") (pinfunction "D8_8") (pintype "passive"))
      (node (ref "R35") (pin "2") (pinfunction "2_2") (pintype "passive"))
      (node (ref "R37") (pin "1") (pinfunction "1_1") (pintype "passive"))
      (node (ref "U10") (pin "6") (pinfunction "OUT_6") (pintype "passive"))
    )
    (net (code "32") (name "OUT2") (class "Default")
      (node (ref "C52") (pin "2") (pinfunction "2_2") (pintype "passive"))
      (node (ref "J7") (pin "2") (pinfunction "2_2") (pintype "passive"))
      (node (ref "Q4") (pin "1") (pinfunction "S1_1") (pintype "passive"))
      (node (ref "Q4") (pin "2") (pinfunction "S2_2") (pintype "passive"))
      (node (ref "Q4") (pin "3") (pinfunction "S3_3") (pintype "passive"))
      (node (ref "Q5") (pin "5") (pinfunction "D_5") (pintype "passive"))
      (node (ref "Q5") (pin "6") (pinfunction "D6_6") (pintype "passive"))
      (node (ref "Q5") (pin "7") (pinfunction "D7_7") (pintype "passive"))
      (node (ref "Q5") (pin "8") (pinfunction "D8_8") (pintype "passive"))
      (node (ref "R41") (pin "2") (pinfunction "2_2") (pintype "passive"))
      (node (ref "R44") (pin "1") (pinfunction "1_1") (pintype "passive"))
      (node (ref "U11") (pin "6") (pinfunction "OUT_6") (pintype "passive"))
    )
    (net (code "33") (name "OUT3") (class "Default")
      (node (ref "C58") (pin "2") (pinfunction "2_2") (pintype "passive"))
      (node (ref "J7") (pin "1") (pinfunction "1_1") (pintype "passive"))
      (node (ref "Q6") (pin "1") (pinfunction "S1_1") (pintype "passive"))
      (node (ref "Q6") (pin "2") (pinfunction "S2_2") (pintype "passive"))
      (node (ref "Q6") (pin "3") (pinfunction "S3_3") (pintype "passive"))
      (node (ref "Q7") (pin "5") (pinfunction "D_5") (pintype "passive"))
      (node (ref "Q7") (pin "6") (pinfunction "D6_6") (pintype "passive"))
      (node (ref "Q7") (pin "7") (pinfunction "D7_7") (pintype "passive"))
      (node (ref "Q7") (pin "8") (pinfunction "D8_8") (pintype "passive"))
      (node (ref "R48") (pin "2") (pinfunction "2_2") (pintype "passive"))
      (node (ref "R51") (pin "1") (pinfunction "1_1") (pintype "passive"))
      (node (ref "U13") (pin "6") (pinfunction "OUT_6") (pintype "passive"))
    )
    (net (code "34") (name "TIM1_CH1") (class "Default")
      (node (ref "C48") (pin "1") (pinfunction "1_1") (pintype "passive"))
      (node (ref "U10") (pin "2") (pinfunction "HIN_2") (pintype "passive"))
    )
    (net (code "35") (name "TIM1_CH1N") (class "Default")
      (node (ref "C47") (pin "1") (pinfunction "1_1") (pintype "passive"))
      (node (ref "U10") (pin "1") (pinfunction "LIN_1") (pintype "passive"))
    )
    (net (code "36") (name "TIM1_CH2") (class "Default")
      (node (ref "C54") (pin "1") (pinfunction "1_1") (pintype "passive"))
      (node (ref "U11") (pin "2") (pinfunction "HIN_2") (pintype "passive"))
    )
    (net (code "37") (name "TIM1_CH2N") (class "Default")
      (node (ref "C53") (pin "1") (pinfunction "1_1") (pintype "passive"))
      (node (ref "U11") (pin "1") (pinfunction "LIN_1") (pintype "passive"))
    )
    (net (code "38") (name "TIM1_CH3") (class "Default")
      (node (ref "C61") (pin "1") (pinfunction "1_1") (pintype "passive"))
      (node (ref "U13") (pin "2") (pinfunction "HIN_2") (pintype "passive"))
    )
    (net (code "39") (name "TIM1_CH3N") (class "Default")
      (node (ref "C60") (pin "1") (pinfunction "1_1") (pintype "passive"))
      (node (ref "U13") (pin "1") (pinfunction "LIN_1") (pintype "passive"))
    )
    (net (code "40") (name "V+") (class "Default")
      (node (ref "C27") (pin "2") (pinfunction "2_2") (pintype "passive"))
      (node (ref "C28") (pin "2") (pinfunction "2_2") (pintype "passive"))
      (node (ref "C29") (pin "2") (pinfunction "2_2") (pintype "passive"))
      (node (ref "C30") (pin "2") (pinfunction "2_2") (pintype "passive"))
      (node (ref "C31") (pin "2") (pinfunction "2_2") (pintype "passive"))
      (node (ref "C32") (pin "2") (pinfunction "2_2") (pintype "passive"))
      (node (ref "C33") (pin "2") (pinfunction "2_2") (pintype "passive"))
      (node (ref "C34") (pin "2") (pinfunction "2_2") (pintype "passive"))
      (node (ref "C35") (pin "2") (pinfunction "2_2") (pintype "passive"))
      (node (ref "C36") (pin "2") (pinfunction "2_2") (pintype "passive"))
      (node (ref "C37") (pin "2") (pinfunction "2_2") (pintype "passive"))
      (node (ref "C38") (pin "2") (pinfunction "2_2") (pintype "passive"))
      (node (ref "C39") (pin "2") (pinfunction "2_2") (pintype "passive"))
      (node (ref "C40") (pin "2") (pinfunction "2_2") (pintype "passive"))
      (node (ref "C41") (pin "1") (pinfunction "1_1") (pintype "passive"))
      (node (ref "C44") (pin "1") (pinfunction "1_1") (pintype "passive"))
      (node (ref "D20") (pin "C") (pinfunction "C_C") (pintype "passive"))
      (node (ref "J5") (pin "1") (pinfunction "1_1") (pintype "passive"))
      (node (ref "Q2") (pin "5") (pinfunction "D_5") (pintype "passive"))
      (node (ref "Q2") (pin "6") (pinfunction "D6_6") (pintype "passive"))
      (node (ref "Q2") (pin "7") (pinfunction "D7_7") (pintype "passive"))
      (node (ref "Q2") (pin "8") (pinfunction "D8_8") (pintype "passive"))
      (node (ref "Q4") (pin "5") (pinfunction "D_5") (pintype "passive"))
      (node (ref "Q4") (pin "6") (pinfunction "D6_6") (pintype "passive"))
      (node (ref "Q4") (pin "7") (pinfunction "D7_7") (pintype "passive"))
      (node (ref "Q4") (pin "8") (pinfunction "D8_8") (pintype "passive"))
      (node (ref "Q6") (pin "5") (pinfunction "D_5") (pintype "passive"))
      (node (ref "Q6") (pin "6") (pinfunction "D6_6") (pintype "passive"))
      (node (ref "Q6") (pin "7") (pinfunction "D7_7") (pintype "passive"))
      (node (ref "Q6") (pin "8") (pinfunction "D8_8") (pintype "passive"))
      (node (ref "U9") (pin "10") (pinfunction "VCC10_10") (pintype "passive"))
      (node (ref "U9") (pin "4") (pinfunction "EN_4") (pintype "passive"))
      (node (ref "U9") (pin "9") (pinfunction "VCC9_9") (pintype "passive"))
    )
    (net (code "41") (name "Vshunt_1 +") (class "Default")
      (node (ref "Q3") (pin "1") (pinfunction "S1_1") (pintype "passive"))
      (node (ref "Q3") (pin "2") (pinfunction "S2_2") (pintype "passive"))
      (node (ref "Q3") (pin "3") (pinfunction "S3_3") (pintype "passive"))
      (node (ref "R39") (pin "2") (pinfunction "2_2") (pintype "passive"))
      (node (ref "R54") (pin "1") (pinfunction "1_1") (pintype "passive"))
    )
    (net (code "42") (name "Vshunt_1-") (class "Default")
      (node (ref "JP1") (pin "1") (pinfunction "1_1") (pintype "passive"))
    )
    (net (code "43") (name "Vshunt_2 +") (class "Default")
      (node (ref "Q5") (pin "1") (pinfunction "S1_1") (pintype "passive"))
      (node (ref "Q5") (pin "2") (pinfunction "S2_2") (pintype "passive"))
      (node (ref "Q5") (pin "3") (pinfunction "S3_3") (pintype "passive"))
      (node (ref "R45") (pin "2") (pinfunction "2_2") (pintype "passive"))
      (node (ref "R55") (pin "1") (pinfunction "1_1") (pintype "passive"))
    )
    (net (code "44") (name "Vshunt_2-") (class "Default")
      (node (ref "JP2") (pin "1") (pinfunction "1_1") (pintype "passive"))
    )
    (net (code "45") (name "Vshunt_3 +") (class "Default")
      (node (ref "Q7") (pin "1") (pinfunction "S1_1") (pintype "passive"))
      (node (ref "Q7") (pin "2") (pinfunction "S2_2") (pintype "passive"))
      (node (ref "Q7") (pin "3") (pinfunction "S3_3") (pintype "passive"))
      (node (ref "R52") (pin "2") (pinfunction "2_2") (pintype "passive"))
      (node (ref "R56") (pin "1") (pinfunction "1_1") (pintype "passive"))
    )
    (net (code "46") (name "Vshunt_3-") (class "Default")
      (node (ref "JP3") (pin "1") (pinfunction "1_1") (pintype "passive"))
    )
    (net (code "47") (name "unconnected-(U9-SYNC-Pad3)") (class "Default")
      (node (ref "U9") (pin "3") (pinfunction "SYNC_3") (pintype "passive+no_connect"))
    )
    (net (code "48") (name "unconnected-(U12-PG-Pad3)") (class "Default")
      (node (ref "U12") (pin "3") (pinfunction "PG_3") (pintype "passive+no_connect"))
    )
    (net (code "49") (name "unconnected-(U14-PG-Pad3)") (class "Default")
      (node (ref "U14") (pin "3") (pinfunction "PG_3") (pintype "passive+no_connect"))
    )
  )
)
